# ESPixelGECE.net
KiCad netlist of a schematic drawn in EAGLE
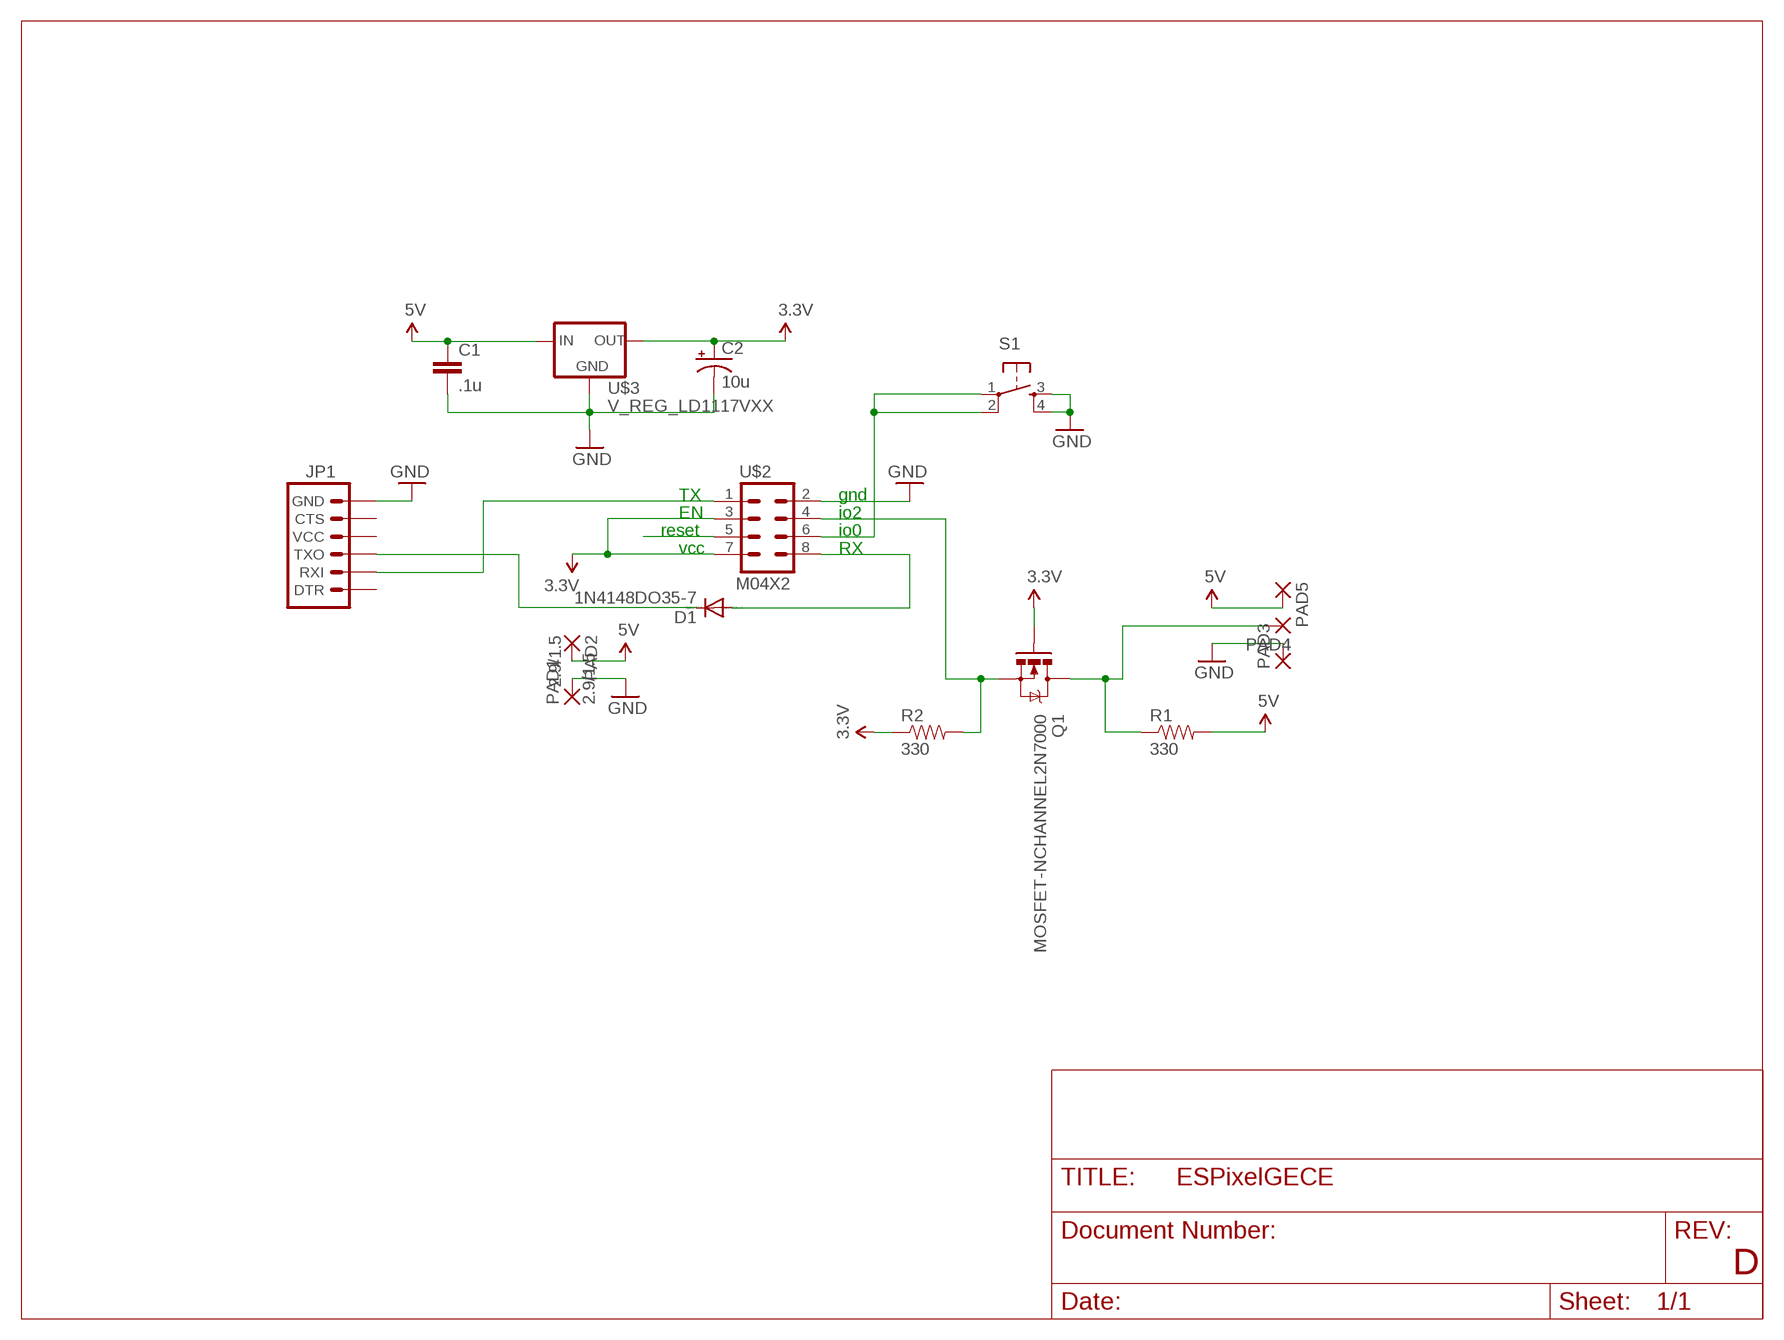
[diagram p0: schematic, sheet 1]

(export (version "E")
  (design (tool "Eeschema 10.0.6"))
  (components
    (comp (ref "C1")
      (value ".1u")
      (footprint "eagle-import:CAP-PTH-SMALLEZ")
      (libsource (lib "eagle-import") (part "CAPEZ"))
    )
    (comp (ref "C2")
      (value "10u")
      (footprint "eagle-import:CPOL-RADIAL-10UF-25V")
      (libsource (lib "eagle-import") (part "CAP_POLPTH2"))
    )
    (comp (ref "D1")
      (value "1N4148DO35-7")
      (footprint "eagle-import:DO35-7")
      (libsource (lib "eagle-import") (part "1N4148DO35-7"))
    )
    (comp (ref "JP1")
      (value "ARDUINO_SERIAL_PROGRAMLOCK")
      (footprint "eagle-import:1X06_LOCK")
      (libsource (lib "eagle-import") (part "ARDUINO_SERIAL_PROGRAMLOCK"))
    )
    (comp (ref "PAD1")
      (value "2.9/1.5")
      (footprint "eagle-import:2.9_1.5")
      (libsource (lib "eagle-import") (part "2.9/1.5"))
    )
    (comp (ref "PAD2")
      (value "2.9/1.5")
      (footprint "eagle-import:2.9_1.5")
      (libsource (lib "eagle-import") (part "2.9/1.5"))
    )
    (comp (ref "PAD3")
      (value "2,15/1,0")
      (footprint "eagle-import:2,15_1,0")
      (libsource (lib "eagle-import") (part "2,15/1,0"))
    )
    (comp (ref "PAD4")
      (value "2,15/1,0")
      (footprint "eagle-import:2,15_1,0")
      (libsource (lib "eagle-import") (part "2,15/1,0"))
    )
    (comp (ref "PAD5")
      (value "2,15/1,0")
      (footprint "eagle-import:2,15_1,0")
      (libsource (lib "eagle-import") (part "2,15/1,0"))
    )
    (comp (ref "Q1")
      (value "MOSFET-NCHANNEL2N7000")
      (footprint "eagle-import:TO-92")
      (libsource (lib "eagle-import") (part "MOSFET-NCHANNEL2N7000"))
    )
    (comp (ref "R1")
      (value "330")
      (footprint "eagle-import:AXIAL-0.3EZ")
      (libsource (lib "eagle-import") (part "RESISTOREZ"))
    )
    (comp (ref "R2")
      (value "330")
      (footprint "eagle-import:AXIAL-0.3EZ")
      (libsource (lib "eagle-import") (part "RESISTOREZ"))
    )
    (comp (ref "S1")
      (value "TAC_SWITCHPTH")
      (footprint "eagle-import:TACTILE-PTH")
      (libsource (lib "eagle-import") (part "TAC_SWITCHPTH"))
    )
    (comp (ref "U$2")
      (value "M04X2")
      (footprint "eagle-import:2X4")
      (libsource (lib "eagle-import") (part "M04X2"))
    )
    (comp (ref "U$3")
      (value "V_REG_LD1117VXX")
      (footprint "eagle-import:78XXL")
      (libsource (lib "eagle-import") (part "V_REG_LD1117VXX"))
    )
  )
  (nets
    (net (code "1") (name "3.3V") (class "Default")
      (node (ref "C2") (pin "1") (pinfunction "+_1") (pintype "passive"))
      (node (ref "Q1") (pin "2") (pinfunction "G_2") (pintype "passive"))
      (node (ref "R2") (pin "P$1") (pinfunction "1_P$1") (pintype "passive"))
      (node (ref "U$2") (pin "3") (pinfunction "3_3") (pintype "passive"))
      (node (ref "U$2") (pin "7") (pinfunction "7_7") (pintype "passive"))
      (node (ref "U$3") (pin "GND") (pinfunction "OUT_GND") (pintype "output"))
    )
    (net (code "2") (name "5V") (class "Default")
      (node (ref "C1") (pin "1") (pinfunction "1_1") (pintype "passive"))
      (node (ref "PAD2") (pin "1") (pinfunction "P_1") (pintype "passive"))
      (node (ref "PAD5") (pin "1") (pinfunction "P_1") (pintype "passive"))
      (node (ref "R1") (pin "P$2") (pinfunction "2_P$2") (pintype "passive"))
      (node (ref "U$3") (pin "OUT") (pinfunction "IN_OUT") (pintype "input"))
    )
    (net (code "3") (name "GND") (class "Default")
      (node (ref "C1") (pin "2") (pinfunction "2_2") (pintype "passive"))
      (node (ref "C2") (pin "2") (pinfunction "-_2") (pintype "passive"))
      (node (ref "JP1") (pin "6") (pinfunction "GND_6") (pintype "passive"))
      (node (ref "PAD1") (pin "1") (pinfunction "P_1") (pintype "passive"))
      (node (ref "PAD3") (pin "1") (pinfunction "P_1") (pintype "passive"))
      (node (ref "S1") (pin "3") (pinfunction "3_3") (pintype "passive"))
      (node (ref "S1") (pin "4") (pinfunction "4_4") (pintype "passive"))
      (node (ref "U$2") (pin "2") (pinfunction "2_2") (pintype "passive"))
      (node (ref "U$3") (pin "IN") (pinfunction "GND_IN") (pintype "input"))
    )
    (net (code "4") (name "Net-(D1-PadA)") (class "Default")
      (node (ref "D1") (pin "A") (pinfunction "A_A") (pintype "passive"))
      (node (ref "U$2") (pin "8") (pinfunction "8_8") (pintype "passive"))
    )
    (net (code "5") (name "Net-(JP1-RXI)") (class "Default")
      (node (ref "JP1") (pin "2") (pinfunction "RXI_2") (pintype "passive"))
      (node (ref "U$2") (pin "1") (pinfunction "1_1") (pintype "passive"))
    )
    (net (code "6") (name "Net-(JP1-TXO)") (class "Default")
      (node (ref "D1") (pin "C") (pinfunction "C_C") (pintype "passive"))
      (node (ref "JP1") (pin "3") (pinfunction "TXO_3") (pintype "passive"))
    )
    (net (code "7") (name "Net-(PAD4-P)") (class "Default")
      (node (ref "PAD4") (pin "1") (pinfunction "P_1") (pintype "passive"))
      (node (ref "Q1") (pin "3") (pinfunction "D_3") (pintype "passive"))
      (node (ref "R1") (pin "P$1") (pinfunction "1_P$1") (pintype "passive"))
    )
    (net (code "8") (name "Net-(Q1-S)") (class "Default")
      (node (ref "Q1") (pin "1") (pinfunction "S_1") (pintype "passive"))
      (node (ref "R2") (pin "P$2") (pinfunction "2_P$2") (pintype "passive"))
      (node (ref "U$2") (pin "4") (pinfunction "4_4") (pintype "passive"))
    )
    (net (code "9") (name "Net-(S1-Pad1)") (class "Default")
      (node (ref "S1") (pin "1") (pinfunction "1_1") (pintype "passive"))
      (node (ref "S1") (pin "2") (pinfunction "2_2") (pintype "passive"))
      (node (ref "U$2") (pin "6") (pinfunction "6_6") (pintype "passive"))
    )
    (net (code "10") (name "unconnected-(JP1-CTS-Pad5)") (class "Default")
      (node (ref "JP1") (pin "5") (pinfunction "CTS_5") (pintype "passive"))
    )
    (net (code "11") (name "unconnected-(JP1-DTR-Pad1)") (class "Default")
      (node (ref "JP1") (pin "1") (pinfunction "DTR_1") (pintype "passive"))
    )
    (net (code "12") (name "unconnected-(JP1-VCC-Pad4)") (class "Default")
      (node (ref "JP1") (pin "4") (pinfunction "VCC_4") (pintype "passive"))
    )
    (net (code "13") (name "unconnected-(U$2-Pad5)") (class "Default")
      (node (ref "U$2") (pin "5") (pinfunction "5_5") (pintype "passive"))
    )
  )
)
